# Brightness.net
KiCad netlist of a schematic drawn in EAGLE
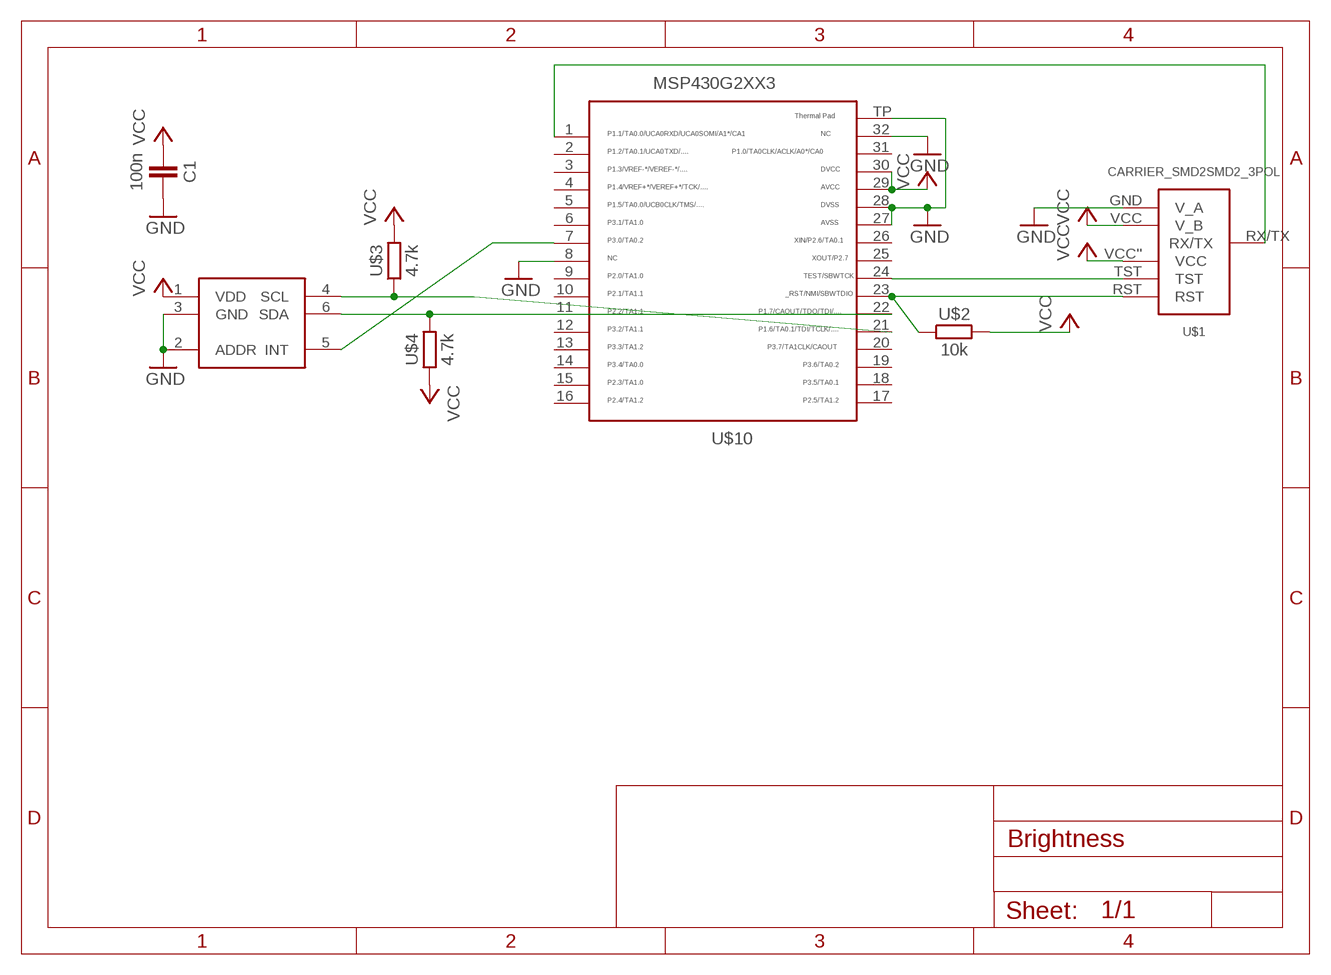
[diagram p0: schematic, sheet 1]

(export (version "E")
  (design (tool "Eeschema 10.0.6"))
  (components
    (comp (ref "C1")
      (value "100n")
      (footprint "eagle-import:603")
      (libsource (lib "eagle-import") (part "CAPACITOR"))
    )
    (comp (ref "U$1")
      (value "CARRIER_SMD2SMD2_3POL")
      (footprint "eagle-import:CARRIER_SMD2_3POL")
      (libsource (lib "eagle-import") (part "CARRIER_SMD2SMD2_3POL"))
    )
    (comp (ref "U$2")
      (value "10k")
      (footprint "eagle-import:603")
      (libsource (lib "eagle-import") (part "RESISTOR0603"))
    )
    (comp (ref "U$3")
      (value "4.7k")
      (footprint "eagle-import:603")
      (libsource (lib "eagle-import") (part "RESISTOR0603"))
    )
    (comp (ref "U$4")
      (value "4.7k")
      (footprint "eagle-import:603")
      (libsource (lib "eagle-import") (part "RESISTOR0603"))
    )
    (comp (ref "U$10")
      (value "MSP430G2553")
      (footprint "eagle-import:QFN32")
      (libsource (lib "eagle-import") (part "MSP430G2553"))
    )
    (comp (ref "U$27")
      (value "TSL2561T")
      (footprint "eagle-import:TSL2561T")
      (libsource (lib "eagle-import") (part "TSL2561T"))
    )
  )
  (nets
    (net (code "1") (name "GND") (class "Default")
      (node (ref "C1") (pin "2") (pinfunction "2_2") (pintype "passive"))
      (node (ref "U$1") (pin "GND") (pinfunction "V_A_GND") (pintype "bidirectional"))
      (node (ref "U$10") (pin "27") (pinfunction "27_27") (pintype "bidirectional"))
      (node (ref "U$10") (pin "28") (pinfunction "28_28") (pintype "bidirectional"))
      (node (ref "U$10") (pin "32") (pinfunction "32_32") (pintype "bidirectional"))
      (node (ref "U$10") (pin "8") (pinfunction "8_8") (pintype "bidirectional"))
      (node (ref "U$10") (pin "TP") (pinfunction "TP_TP") (pintype "bidirectional"))
      (node (ref "U$27") (pin "2") (pinfunction "ADDR_2") (pintype "output"))
      (node (ref "U$27") (pin "3") (pinfunction "GND_3") (pintype "output"))
    )
    (net (code "2") (name "Net-(U$1-PadRST)") (class "Default")
      (node (ref "U$1") (pin "RST") (pinfunction "RST_RST") (pintype "bidirectional"))
      (node (ref "U$10") (pin "23") (pinfunction "23_23") (pintype "bidirectional"))
      (node (ref "U$2") (pin "1") (pinfunction "1_1") (pintype "passive"))
    )
    (net (code "3") (name "Net-(U$1-PadRX{slash}TX)") (class "Default")
      (node (ref "U$1") (pin "RX/TX") (pinfunction "RX/TX_RX/TX") (pintype "bidirectional"))
      (node (ref "U$10") (pin "1") (pinfunction "1_1") (pintype "bidirectional"))
    )
    (net (code "4") (name "Net-(U$1-PadTST)") (class "Default")
      (node (ref "U$1") (pin "TST") (pinfunction "TST_TST") (pintype "bidirectional"))
      (node (ref "U$10") (pin "24") (pinfunction "24_24") (pintype "bidirectional"))
    )
    (net (code "5") (name "Net-(U$27-INT)") (class "Default")
      (node (ref "U$10") (pin "7") (pinfunction "7_7") (pintype "bidirectional"))
      (node (ref "U$27") (pin "5") (pinfunction "INT_5") (pintype "output"))
    )
    (net (code "6") (name "Net-(U$27-SCL)") (class "Default")
      (node (ref "U$10") (pin "21") (pinfunction "21_21") (pintype "bidirectional"))
      (node (ref "U$27") (pin "4") (pinfunction "SCL_4") (pintype "output"))
      (node (ref "U$3") (pin "1") (pinfunction "1_1") (pintype "passive"))
    )
    (net (code "7") (name "Net-(U$27-SDA)") (class "Default")
      (node (ref "U$10") (pin "22") (pinfunction "22_22") (pintype "bidirectional"))
      (node (ref "U$27") (pin "6") (pinfunction "SDA_6") (pintype "output"))
      (node (ref "U$4") (pin "2") (pinfunction "2_2") (pintype "passive"))
    )
    (net (code "8") (name "VCC") (class "Default")
      (node (ref "C1") (pin "1") (pinfunction "1_1") (pintype "passive"))
      (node (ref "U$1") (pin "VCC") (pinfunction "V_B_VCC") (pintype "bidirectional"))
      (node (ref "U$1") (pin "VCC''") (pinfunction "VCC_VCC''") (pintype "bidirectional"))
      (node (ref "U$10") (pin "29") (pinfunction "29_29") (pintype "bidirectional"))
      (node (ref "U$10") (pin "30") (pinfunction "30_30") (pintype "bidirectional"))
      (node (ref "U$2") (pin "2") (pinfunction "2_2") (pintype "passive"))
      (node (ref "U$27") (pin "1") (pinfunction "VDD_1") (pintype "output"))
      (node (ref "U$3") (pin "2") (pinfunction "2_2") (pintype "passive"))
      (node (ref "U$4") (pin "1") (pinfunction "1_1") (pintype "passive"))
    )
    (net (code "9") (name "unconnected-(U$10-Pad2)") (class "Default")
      (node (ref "U$10") (pin "2") (pinfunction "2_2") (pintype "bidirectional"))
    )
    (net (code "10") (name "unconnected-(U$10-Pad3)") (class "Default")
      (node (ref "U$10") (pin "3") (pinfunction "3_3") (pintype "bidirectional"))
    )
    (net (code "11") (name "unconnected-(U$10-Pad4)") (class "Default")
      (node (ref "U$10") (pin "4") (pinfunction "4_4") (pintype "bidirectional"))
    )
    (net (code "12") (name "unconnected-(U$10-Pad5)") (class "Default")
      (node (ref "U$10") (pin "5") (pinfunction "5_5") (pintype "bidirectional"))
    )
    (net (code "13") (name "unconnected-(U$10-Pad6)") (class "Default")
      (node (ref "U$10") (pin "6") (pinfunction "6_6") (pintype "bidirectional"))
    )
    (net (code "14") (name "unconnected-(U$10-Pad9)") (class "Default")
      (node (ref "U$10") (pin "9") (pinfunction "9_9") (pintype "bidirectional"))
    )
    (net (code "15") (name "unconnected-(U$10-Pad10)") (class "Default")
      (node (ref "U$10") (pin "10") (pinfunction "10_10") (pintype "bidirectional"))
    )
    (net (code "16") (name "unconnected-(U$10-Pad11)") (class "Default")
      (node (ref "U$10") (pin "11") (pinfunction "11_11") (pintype "bidirectional"))
    )
    (net (code "17") (name "unconnected-(U$10-Pad12)") (class "Default")
      (node (ref "U$10") (pin "12") (pinfunction "12_12") (pintype "bidirectional"))
    )
    (net (code "18") (name "unconnected-(U$10-Pad13)") (class "Default")
      (node (ref "U$10") (pin "13") (pinfunction "13_13") (pintype "bidirectional"))
    )
    (net (code "19") (name "unconnected-(U$10-Pad14)") (class "Default")
      (node (ref "U$10") (pin "14") (pinfunction "14_14") (pintype "bidirectional"))
    )
    (net (code "20") (name "unconnected-(U$10-Pad15)") (class "Default")
      (node (ref "U$10") (pin "15") (pinfunction "15_15") (pintype "bidirectional"))
    )
    (net (code "21") (name "unconnected-(U$10-Pad16)") (class "Default")
      (node (ref "U$10") (pin "16") (pinfunction "16_16") (pintype "bidirectional"))
    )
    (net (code "22") (name "unconnected-(U$10-Pad17)") (class "Default")
      (node (ref "U$10") (pin "17") (pinfunction "17_17") (pintype "bidirectional"))
    )
    (net (code "23") (name "unconnected-(U$10-Pad18)") (class "Default")
      (node (ref "U$10") (pin "18") (pinfunction "18_18") (pintype "bidirectional"))
    )
    (net (code "24") (name "unconnected-(U$10-Pad19)") (class "Default")
      (node (ref "U$10") (pin "19") (pinfunction "19_19") (pintype "bidirectional"))
    )
    (net (code "25") (name "unconnected-(U$10-Pad20)") (class "Default")
      (node (ref "U$10") (pin "20") (pinfunction "20_20") (pintype "bidirectional"))
    )
    (net (code "26") (name "unconnected-(U$10-Pad25)") (class "Default")
      (node (ref "U$10") (pin "25") (pinfunction "25_25") (pintype "bidirectional"))
    )
    (net (code "27") (name "unconnected-(U$10-Pad26)") (class "Default")
      (node (ref "U$10") (pin "26") (pinfunction "26_26") (pintype "bidirectional"))
    )
    (net (code "28") (name "unconnected-(U$10-Pad31)") (class "Default")
      (node (ref "U$10") (pin "31") (pinfunction "31_31") (pintype "bidirectional"))
    )
  )
)
